# ATTAMI-IR_shield_V2.net
KiCad netlist of a schematic drawn in EAGLE
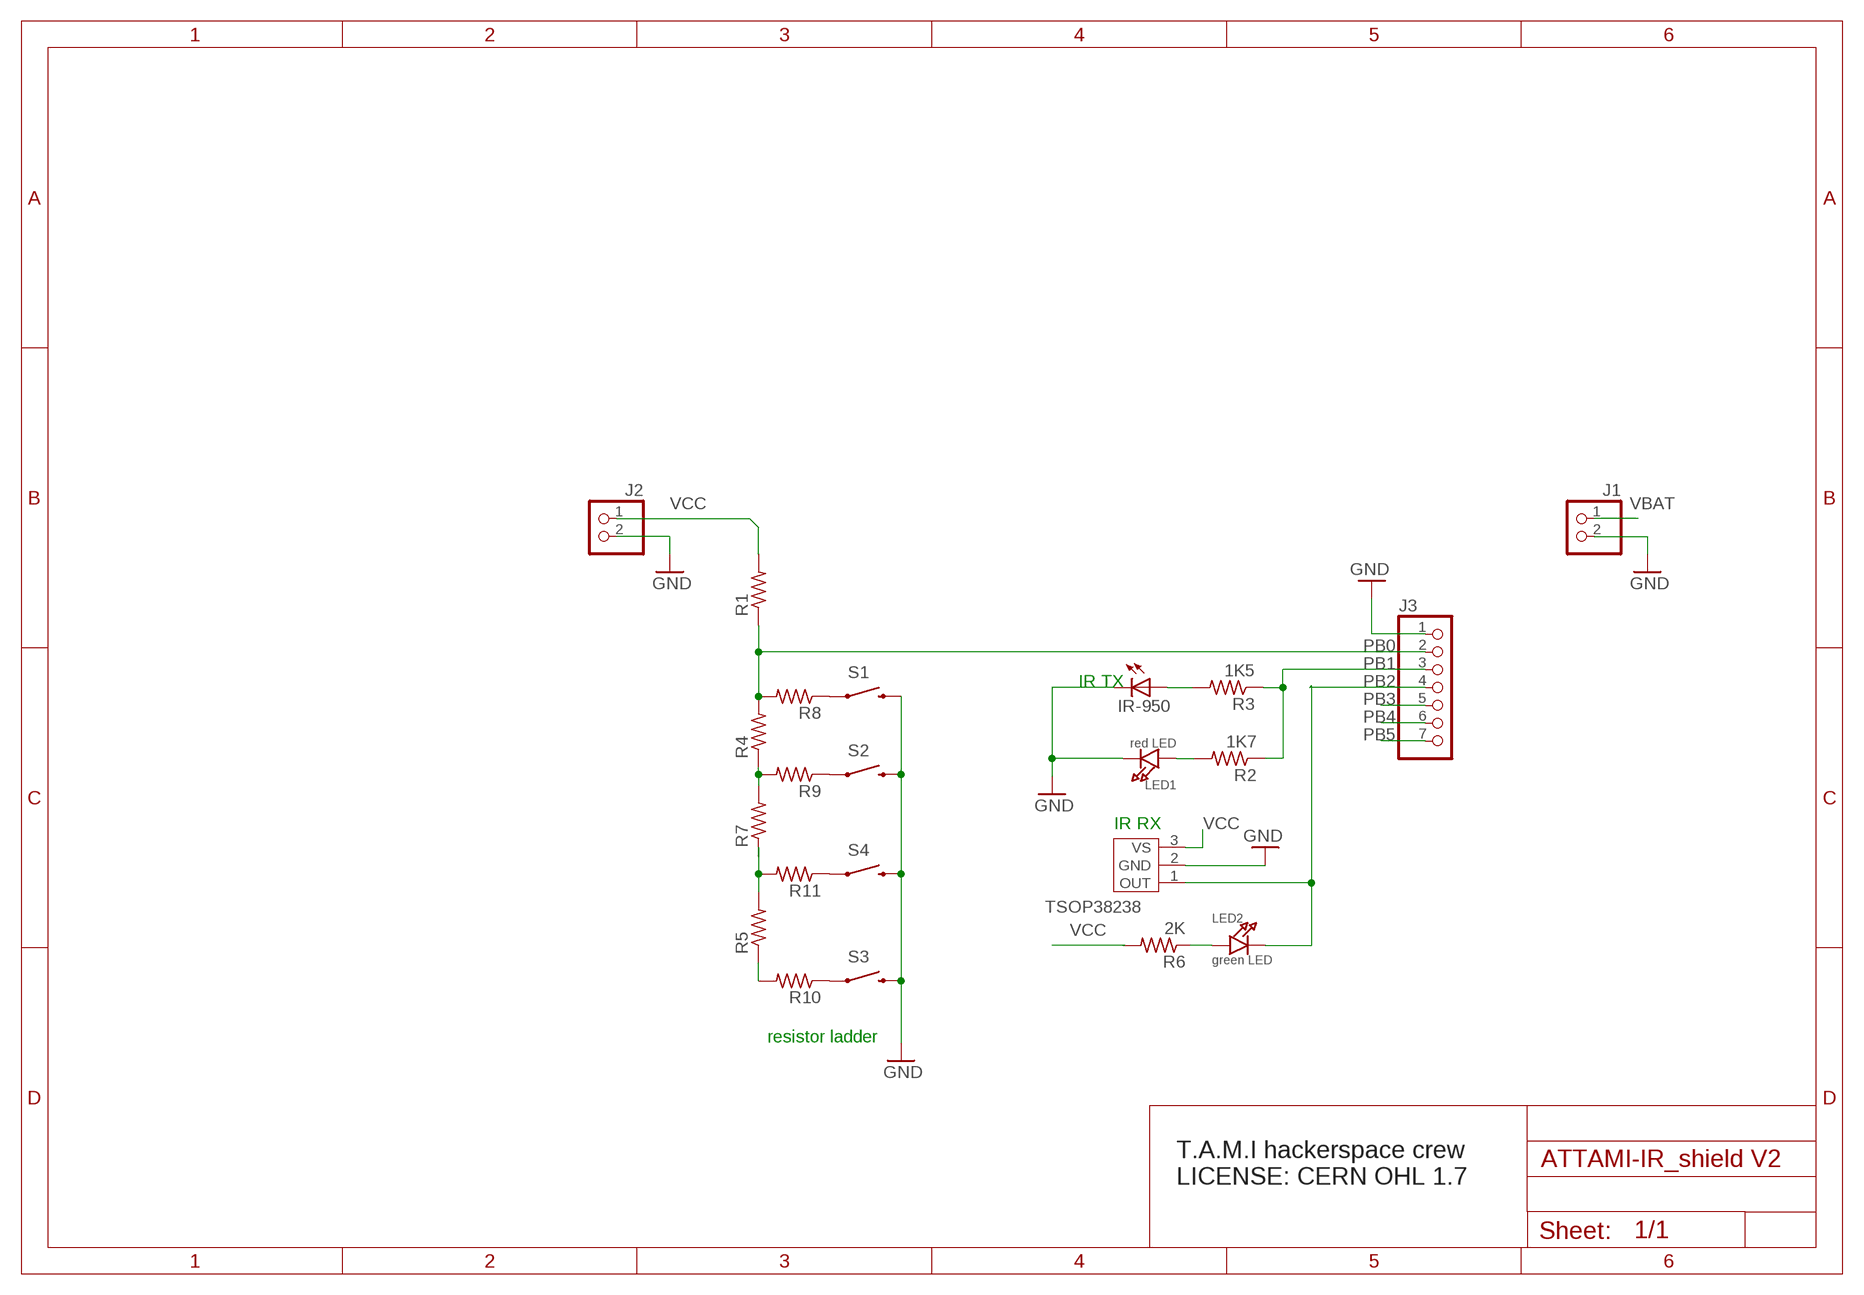
[diagram p0: schematic, sheet 1]

(export (version "E")
  (design (tool "Eeschema 10.0.6"))
  (components
    (comp (ref "IR-950")
      (value "LEDIRL80A")
      (footprint "eagle-import:IRL80A")
      (libsource (lib "eagle-import") (part "LEDIRL80A"))
    )
    (comp (ref "J1")
      (value "HEADER-1X2ROUND")
      (footprint "eagle-import:1X02_ROUND")
      (libsource (lib "eagle-import") (part "HEADER-1X2ROUND"))
    )
    (comp (ref "J2")
      (value "HEADER-1X2ROUND")
      (footprint "eagle-import:1X02_ROUND")
      (libsource (lib "eagle-import") (part "HEADER-1X2ROUND"))
    )
    (comp (ref "J3")
      (value "HEADER-1X7ROUND")
      (footprint "eagle-import:1X07_ROUND")
      (libsource (lib "eagle-import") (part "HEADER-1X7ROUND"))
    )
    (comp (ref "LED1")
      (value "red LED")
      (footprint "eagle-import:CHIPLED_0805")
      (libsource (lib "eagle-import") (part "LED0805"))
    )
    (comp (ref "LED2")
      (value "green LED")
      (footprint "eagle-import:CHIPLED_0805")
      (libsource (lib "eagle-import") (part "LED0805"))
    )
    (comp (ref "R1")
      (value "R-US_M0805")
      (footprint "eagle-import:M0805")
      (libsource (lib "eagle-import") (part "R-US_M0805"))
    )
    (comp (ref "R2")
      (value "1K7")
      (footprint "eagle-import:M0805")
      (libsource (lib "eagle-import") (part "R-US_M0805"))
    )
    (comp (ref "R3")
      (value "1K5")
      (footprint "eagle-import:M0805")
      (libsource (lib "eagle-import") (part "R-US_M0805"))
    )
    (comp (ref "R4")
      (value "R-US_M0805")
      (footprint "eagle-import:M0805")
      (libsource (lib "eagle-import") (part "R-US_M0805"))
    )
    (comp (ref "R5")
      (value "R-US_M0805")
      (footprint "eagle-import:M0805")
      (libsource (lib "eagle-import") (part "R-US_M0805"))
    )
    (comp (ref "R6")
      (value "2K")
      (footprint "eagle-import:M0805")
      (libsource (lib "eagle-import") (part "R-US_M0805"))
    )
    (comp (ref "R7")
      (value "R-US_M0805")
      (footprint "eagle-import:M0805")
      (libsource (lib "eagle-import") (part "R-US_M0805"))
    )
    (comp (ref "R8")
      (value "R-US_M0805")
      (footprint "eagle-import:M0805")
      (libsource (lib "eagle-import") (part "R-US_M0805"))
    )
    (comp (ref "R9")
      (value "R-US_M0805")
      (footprint "eagle-import:M0805")
      (libsource (lib "eagle-import") (part "R-US_M0805"))
    )
    (comp (ref "R10")
      (value "R-US_M0805")
      (footprint "eagle-import:M0805")
      (libsource (lib "eagle-import") (part "R-US_M0805"))
    )
    (comp (ref "R11")
      (value "R-US_M0805")
      (footprint "eagle-import:M0805")
      (libsource (lib "eagle-import") (part "R-US_M0805"))
    )
    (comp (ref "S1")
      (value "SWITCH-MOMENTARY-2-SMD-1101NE")
      (footprint "eagle-import:TACTILE-SWITCH-1101NE")
      (libsource (lib "eagle-import") (part "SWITCH-MOMENTARY-2-SMD-1101NE"))
    )
    (comp (ref "S2")
      (value "SWITCH-MOMENTARY-2-SMD-1101NE")
      (footprint "eagle-import:TACTILE-SWITCH-1101NE")
      (libsource (lib "eagle-import") (part "SWITCH-MOMENTARY-2-SMD-1101NE"))
    )
    (comp (ref "S3")
      (value "SWITCH-MOMENTARY-2-SMD-1101NE")
      (footprint "eagle-import:TACTILE-SWITCH-1101NE")
      (libsource (lib "eagle-import") (part "SWITCH-MOMENTARY-2-SMD-1101NE"))
    )
    (comp (ref "S4")
      (value "SWITCH-MOMENTARY-2-SMD-1101NE")
      (footprint "eagle-import:TACTILE-SWITCH-1101NE")
      (libsource (lib "eagle-import") (part "SWITCH-MOMENTARY-2-SMD-1101NE"))
    )
    (comp (ref "TSOP38238")
      (value "TSOP382")
      (footprint "eagle-import:3P-2.54-4.8X5X6.95H")
      (libsource (lib "eagle-import") (part "TSOP382"))
    )
  )
  (nets
    (net (code "1") (name "/PB0") (class "Default")
      (node (ref "J3") (pin "2") (pinfunction "2_2") (pintype "passive"))
      (node (ref "R1") (pin "1") (pinfunction "1_1") (pintype "passive"))
      (node (ref "R4") (pin "2") (pinfunction "2_2") (pintype "passive"))
      (node (ref "R8") (pin "2") (pinfunction "2_2") (pintype "passive"))
    )
    (net (code "2") (name "/PB1") (class "Default")
      (node (ref "J3") (pin "3") (pinfunction "3_3") (pintype "passive"))
      (node (ref "R2") (pin "1") (pinfunction "1_1") (pintype "passive"))
      (node (ref "R3") (pin "1") (pinfunction "1_1") (pintype "passive"))
    )
    (net (code "3") (name "/PB2") (class "Default")
      (node (ref "J3") (pin "4") (pinfunction "4_4") (pintype "passive"))
      (node (ref "LED2") (pin "C") (pinfunction "C_C") (pintype "passive"))
      (node (ref "TSOP38238") (pin "1") (pinfunction "OUT_1") (pintype "bidirectional"))
    )
    (net (code "4") (name "/PB3") (class "Default")
      (node (ref "J3") (pin "5") (pinfunction "5_5") (pintype "passive"))
    )
    (net (code "5") (name "/PB4") (class "Default")
      (node (ref "J3") (pin "6") (pinfunction "6_6") (pintype "passive"))
    )
    (net (code "6") (name "/PB5") (class "Default")
      (node (ref "J3") (pin "7") (pinfunction "7_7") (pintype "passive"))
    )
    (net (code "7") (name "/VBAT") (class "Default")
      (node (ref "J1") (pin "1") (pinfunction "1_1") (pintype "passive"))
    )
    (net (code "8") (name "/VCC") (class "Default")
      (node (ref "J2") (pin "1") (pinfunction "1_1") (pintype "passive"))
      (node (ref "R1") (pin "2") (pinfunction "2_2") (pintype "passive"))
      (node (ref "TSOP38238") (pin "3") (pinfunction "VS_3") (pintype "bidirectional"))
    )
    (net (code "9") (name "GND") (class "Default")
      (node (ref "IR-950") (pin "K") (pinfunction "C_K") (pintype "passive"))
      (node (ref "J1") (pin "2") (pinfunction "2_2") (pintype "passive"))
      (node (ref "J2") (pin "2") (pinfunction "2_2") (pintype "passive"))
      (node (ref "J3") (pin "1") (pinfunction "1_1") (pintype "passive"))
      (node (ref "LED1") (pin "C") (pinfunction "C_C") (pintype "passive"))
      (node (ref "S1") (pin "P$2") (pinfunction "2_P$2") (pintype "passive"))
      (node (ref "S2") (pin "P$2") (pinfunction "2_P$2") (pintype "passive"))
      (node (ref "S3") (pin "P$2") (pinfunction "2_P$2") (pintype "passive"))
      (node (ref "S4") (pin "P$2") (pinfunction "2_P$2") (pintype "passive"))
      (node (ref "TSOP38238") (pin "2") (pinfunction "GND_2") (pintype "bidirectional"))
    )
    (net (code "10") (name "Net-(IR-950-PadA)") (class "Default")
      (node (ref "IR-950") (pin "A") (pinfunction "A_A") (pintype "passive"))
      (node (ref "R3") (pin "2") (pinfunction "2_2") (pintype "passive"))
    )
    (net (code "11") (name "Net-(LED1-PadA)") (class "Default")
      (node (ref "LED1") (pin "A") (pinfunction "A_A") (pintype "passive"))
      (node (ref "R2") (pin "2") (pinfunction "2_2") (pintype "passive"))
    )
    (net (code "12") (name "Net-(R4-Pad1)") (class "Default")
      (node (ref "R4") (pin "1") (pinfunction "1_1") (pintype "passive"))
      (node (ref "R7") (pin "2") (pinfunction "2_2") (pintype "passive"))
      (node (ref "R9") (pin "2") (pinfunction "2_2") (pintype "passive"))
    )
    (net (code "13") (name "Net-(R10-Pad2)") (class "Default")
      (node (ref "R10") (pin "2") (pinfunction "2_2") (pintype "passive"))
      (node (ref "R5") (pin "1") (pinfunction "1_1") (pintype "passive"))
    )
    (net (code "14") (name "Net-(R11-Pad2)") (class "Default")
      (node (ref "R11") (pin "2") (pinfunction "2_2") (pintype "passive"))
      (node (ref "R5") (pin "2") (pinfunction "2_2") (pintype "passive"))
    )
    (net (code "15") (name "Net-(S1-1)") (class "Default")
      (node (ref "R8") (pin "1") (pinfunction "1_1") (pintype "passive"))
      (node (ref "S1") (pin "P$1") (pinfunction "1_P$1") (pintype "passive"))
    )
    (net (code "16") (name "Net-(S2-1)") (class "Default")
      (node (ref "R9") (pin "1") (pinfunction "1_1") (pintype "passive"))
      (node (ref "S2") (pin "P$1") (pinfunction "1_P$1") (pintype "passive"))
    )
    (net (code "17") (name "Net-(S3-1)") (class "Default")
      (node (ref "R10") (pin "1") (pinfunction "1_1") (pintype "passive"))
      (node (ref "S3") (pin "P$1") (pinfunction "1_P$1") (pintype "passive"))
    )
    (net (code "18") (name "Net-(S4-1)") (class "Default")
      (node (ref "R11") (pin "1") (pinfunction "1_1") (pintype "passive"))
      (node (ref "S4") (pin "P$1") (pinfunction "1_P$1") (pintype "passive"))
    )
    (net (code "19") (name "unconnected-(LED2-PadA)") (class "Default")
      (node (ref "LED2") (pin "A") (pinfunction "A_A") (pintype "passive"))
    )
    (net (code "20") (name "unconnected-(R6-Pad1)") (class "Default")
      (node (ref "R6") (pin "1") (pinfunction "1_1") (pintype "passive"))
    )
    (net (code "21") (name "unconnected-(R6-Pad2)") (class "Default")
      (node (ref "R6") (pin "2") (pinfunction "2_2") (pintype "passive"))
    )
    (net (code "22") (name "unconnected-(R7-Pad1)") (class "Default")
      (node (ref "R7") (pin "1") (pinfunction "1_1") (pintype "passive"))
    )
  )
)
